# 2ButtonBase.net
KiCad netlist of a schematic drawn in EAGLE
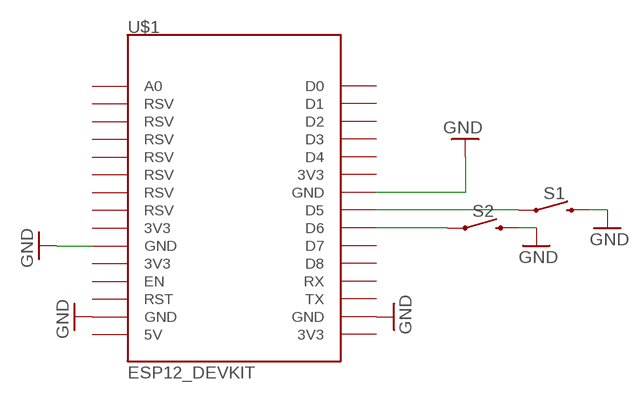
[diagram p0: schematic, sheet 1]

(export (version "E")
  (design (tool "Eeschema 10.0.6"))
  (components
    (comp (ref "S1")
      (value "MOMENTARY-SWITCH-SPST-PTH-12MM")
      (footprint "eagle-import:TACTILE_SWITCH_PTH_12MM")
      (libsource (lib "eagle-import") (part "MOMENTARY-SWITCH-SPST-PTH-12MM"))
    )
    (comp (ref "S2")
      (value "MOMENTARY-SWITCH-SPST-PTH-12MM")
      (footprint "eagle-import:TACTILE_SWITCH_PTH_12MM")
      (libsource (lib "eagle-import") (part "MOMENTARY-SWITCH-SPST-PTH-12MM"))
    )
    (comp (ref "U$1")
      (value "ESP12_DEVKIT")
      (footprint "eagle-import:ESP12_DEVKIT")
      (libsource (lib "eagle-import") (part "ESP12_DEVKIT"))
    )
  )
  (nets
    (net (code "1") (name "GND") (class "Default")
      (node (ref "S1") (pin "3") (pinfunction "2_3") (pintype "passive"))
      (node (ref "S2") (pin "3") (pinfunction "2_3") (pintype "passive"))
      (node (ref "U$1") (pin "GND@0") (pinfunction "GND_GND@0") (pintype "bidirectional"))
      (node (ref "U$1") (pin "GND@1") (pinfunction "GND_GND@1") (pintype "bidirectional"))
      (node (ref "U$1") (pin "GND@2") (pinfunction "GND_GND@2") (pintype "bidirectional"))
      (node (ref "U$1") (pin "GND@3") (pinfunction "GND_GND@3") (pintype "bidirectional"))
    )
    (net (code "2") (name "Net-(S1-Pad1)") (class "Default")
      (node (ref "S1") (pin "1") (pinfunction "1_1") (pintype "passive"))
      (node (ref "U$1") (pin "D5") (pinfunction "D5_D5") (pintype "bidirectional"))
    )
    (net (code "3") (name "Net-(S2-Pad1)") (class "Default")
      (node (ref "S2") (pin "1") (pinfunction "1_1") (pintype "passive"))
      (node (ref "U$1") (pin "D6") (pinfunction "D6_D6") (pintype "bidirectional"))
    )
    (net (code "4") (name "unconnected-(U$1-3V3-Pad3V3@0)") (class "Default")
      (node (ref "U$1") (pin "3V3@0") (pinfunction "3V3_3V3@0") (pintype "bidirectional"))
    )
    (net (code "5") (name "unconnected-(U$1-3V3-Pad3V3@1)") (class "Default")
      (node (ref "U$1") (pin "3V3@1") (pinfunction "3V3_3V3@1") (pintype "bidirectional"))
    )
    (net (code "6") (name "unconnected-(U$1-3V3-Pad3V3@2)") (class "Default")
      (node (ref "U$1") (pin "3V3@2") (pinfunction "3V3_3V3@2") (pintype "bidirectional"))
    )
    (net (code "7") (name "unconnected-(U$1-3V3-Pad3V3@3)") (class "Default")
      (node (ref "U$1") (pin "3V3@3") (pinfunction "3V3_3V3@3") (pintype "bidirectional"))
    )
    (net (code "8") (name "unconnected-(U$1-Pad5V)") (class "Default")
      (node (ref "U$1") (pin "5V") (pinfunction "5V_5V") (pintype "bidirectional"))
    )
    (net (code "9") (name "unconnected-(U$1-PadA0)") (class "Default")
      (node (ref "U$1") (pin "A0") (pinfunction "A0_A0") (pintype "bidirectional"))
    )
    (net (code "10") (name "unconnected-(U$1-PadD0)") (class "Default")
      (node (ref "U$1") (pin "D0") (pinfunction "D0_D0") (pintype "bidirectional"))
    )
    (net (code "11") (name "unconnected-(U$1-PadD1)") (class "Default")
      (node (ref "U$1") (pin "D1") (pinfunction "D1_D1") (pintype "bidirectional"))
    )
    (net (code "12") (name "unconnected-(U$1-PadD2)") (class "Default")
      (node (ref "U$1") (pin "D2") (pinfunction "D2_D2") (pintype "bidirectional"))
    )
    (net (code "13") (name "unconnected-(U$1-PadD3)") (class "Default")
      (node (ref "U$1") (pin "D3") (pinfunction "D3_D3") (pintype "bidirectional"))
    )
    (net (code "14") (name "unconnected-(U$1-PadD4)") (class "Default")
      (node (ref "U$1") (pin "D4") (pinfunction "D4_D4") (pintype "bidirectional"))
    )
    (net (code "15") (name "unconnected-(U$1-PadD7)") (class "Default")
      (node (ref "U$1") (pin "D7") (pinfunction "D7_D7") (pintype "bidirectional"))
    )
    (net (code "16") (name "unconnected-(U$1-PadD8)") (class "Default")
      (node (ref "U$1") (pin "D8") (pinfunction "D8_D8") (pintype "bidirectional"))
    )
    (net (code "17") (name "unconnected-(U$1-PadEN)") (class "Default")
      (node (ref "U$1") (pin "EN") (pinfunction "EN_EN") (pintype "bidirectional"))
    )
    (net (code "18") (name "unconnected-(U$1-PadRST)") (class "Default")
      (node (ref "U$1") (pin "RST") (pinfunction "RST_RST") (pintype "bidirectional"))
    )
    (net (code "19") (name "unconnected-(U$1-PadRX)") (class "Default")
      (node (ref "U$1") (pin "RX") (pinfunction "RX_RX") (pintype "bidirectional"))
    )
    (net (code "20") (name "unconnected-(U$1-PadTX)") (class "Default")
      (node (ref "U$1") (pin "TX") (pinfunction "TX_TX") (pintype "bidirectional"))
    )
    (net (code "21") (name "unconnected-(U$1-RSV-PadGND@4)") (class "Default")
      (node (ref "U$1") (pin "GND@4") (pinfunction "RSV_GND@4") (pintype "bidirectional"))
    )
    (net (code "22") (name "unconnected-(U$1-RSV-PadRSV@0)") (class "Default")
      (node (ref "U$1") (pin "RSV@0") (pinfunction "RSV_RSV@0") (pintype "bidirectional"))
    )
    (net (code "23") (name "unconnected-(U$1-RSV-PadRSV@1)") (class "Default")
      (node (ref "U$1") (pin "RSV@1") (pinfunction "RSV_RSV@1") (pintype "bidirectional"))
    )
    (net (code "24") (name "unconnected-(U$1-RSV-PadRSV@2)") (class "Default")
      (node (ref "U$1") (pin "RSV@2") (pinfunction "RSV_RSV@2") (pintype "bidirectional"))
    )
    (net (code "25") (name "unconnected-(U$1-RSV-PadRSV@3)") (class "Default")
      (node (ref "U$1") (pin "RSV@3") (pinfunction "RSV_RSV@3") (pintype "bidirectional"))
    )
    (net (code "26") (name "unconnected-(U$1-RSV-PadRSV@4)") (class "Default")
      (node (ref "U$1") (pin "RSV@4") (pinfunction "RSV_RSV@4") (pintype "bidirectional"))
    )
    (net (code "27") (name "unconnected-(U$1-RSV-PadRSV@5)") (class "Default")
      (node (ref "U$1") (pin "RSV@5") (pinfunction "RSV_RSV@5") (pintype "bidirectional"))
    )
  )
)
